# LedAlert.net
KiCad netlist of a schematic drawn in Altium Designer
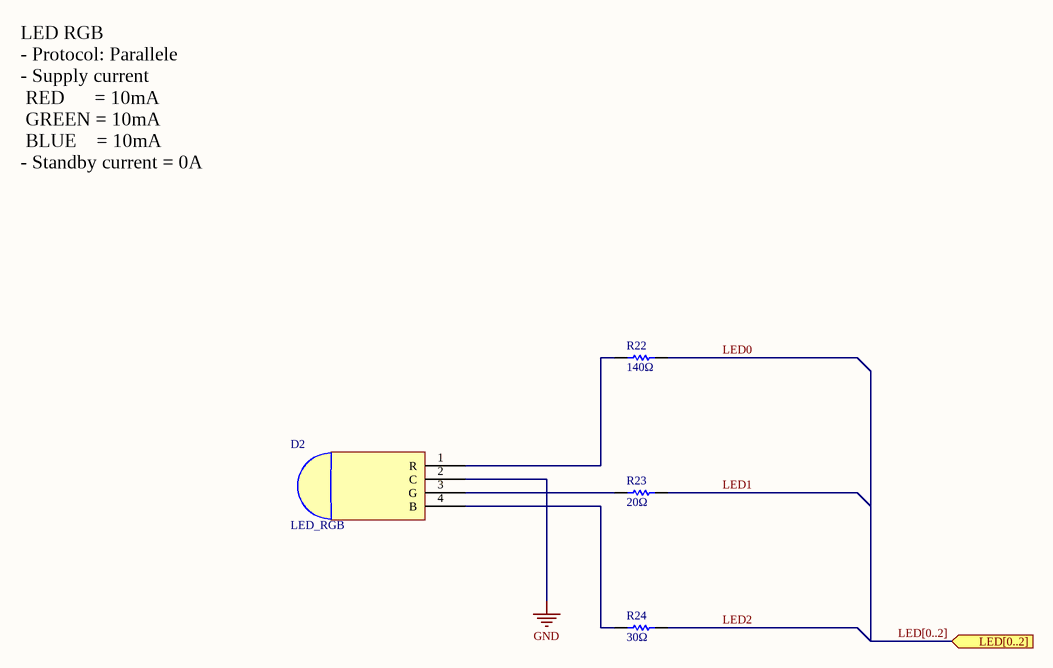
[diagram p0: LedAlert.SchDoc]

(export (version "E")
  (design (tool "Eeschema 10.0.6"))
  (components
    (comp (ref "D2")
      (value "LED_RGB")
      (footprint "LED1")
      (description "LedRGB")
      (fields (field (name "MANUFACTURER") "KINGBRIGHT"))
      (libsource (lib "Electroplant") (part "LED_RGB"))
    )
    (comp (ref "R22")
      (value "140Ω")
      (footprint "R0603")
      (description "Resistor")
      (fields (field (name "MANUFACTURER") "MULTICOMP") (field (name "PUBLISHER") "Altium Limited"))
      (libsource (lib "Miscellaneous Devices") (part "Res1"))
    )
    (comp (ref "R23")
      (value "20Ω")
      (footprint "R0603")
      (description "Resistor")
      (fields (field (name "MANUFACTURER") "MULTICOMP") (field (name "PUBLISHER") "Altium Limited"))
      (libsource (lib "Miscellaneous Devices") (part "Res1"))
    )
    (comp (ref "R24")
      (value "30Ω")
      (footprint "R0603")
      (description "Resistor")
      (fields (field (name "MANUFACTURER") "MULTICOMP") (field (name "PUBLISHER") "Altium Limited"))
      (libsource (lib "Miscellaneous Devices") (part "Res1"))
    )
  )
  (nets
    (net (code "1") (name "/LED0") (class "Default")
      (node (ref "R22") (pin "2") (pinfunction "2_2") (pintype "passive"))
    )
    (net (code "2") (name "/LED1") (class "Default")
      (node (ref "R23") (pin "2") (pinfunction "2_2") (pintype "passive"))
    )
    (net (code "3") (name "/LED2") (class "Default")
      (node (ref "R24") (pin "2") (pinfunction "2_2") (pintype "passive"))
    )
    (net (code "5") (name "GND") (class "Default")
      (node (ref "D2") (pin "2") (pinfunction "C_2") (pintype "passive"))
    )
    (net (code "6") (name "Net-(D2-B)") (class "Default")
      (node (ref "D2") (pin "4") (pinfunction "B_4") (pintype "passive"))
      (node (ref "R24") (pin "1") (pinfunction "1_1") (pintype "passive"))
    )
    (net (code "7") (name "Net-(D2-G)") (class "Default")
      (node (ref "D2") (pin "3") (pinfunction "G_3") (pintype "passive"))
      (node (ref "R23") (pin "1") (pinfunction "1_1") (pintype "passive"))
    )
    (net (code "8") (name "Net-(D2-R)") (class "Default")
      (node (ref "D2") (pin "1") (pinfunction "R_1") (pintype "passive"))
      (node (ref "R22") (pin "1") (pinfunction "1_1") (pintype "passive"))
    )
  )
)
